# WiFi_BT.net
KiCad netlist of a schematic drawn in Altium Designer
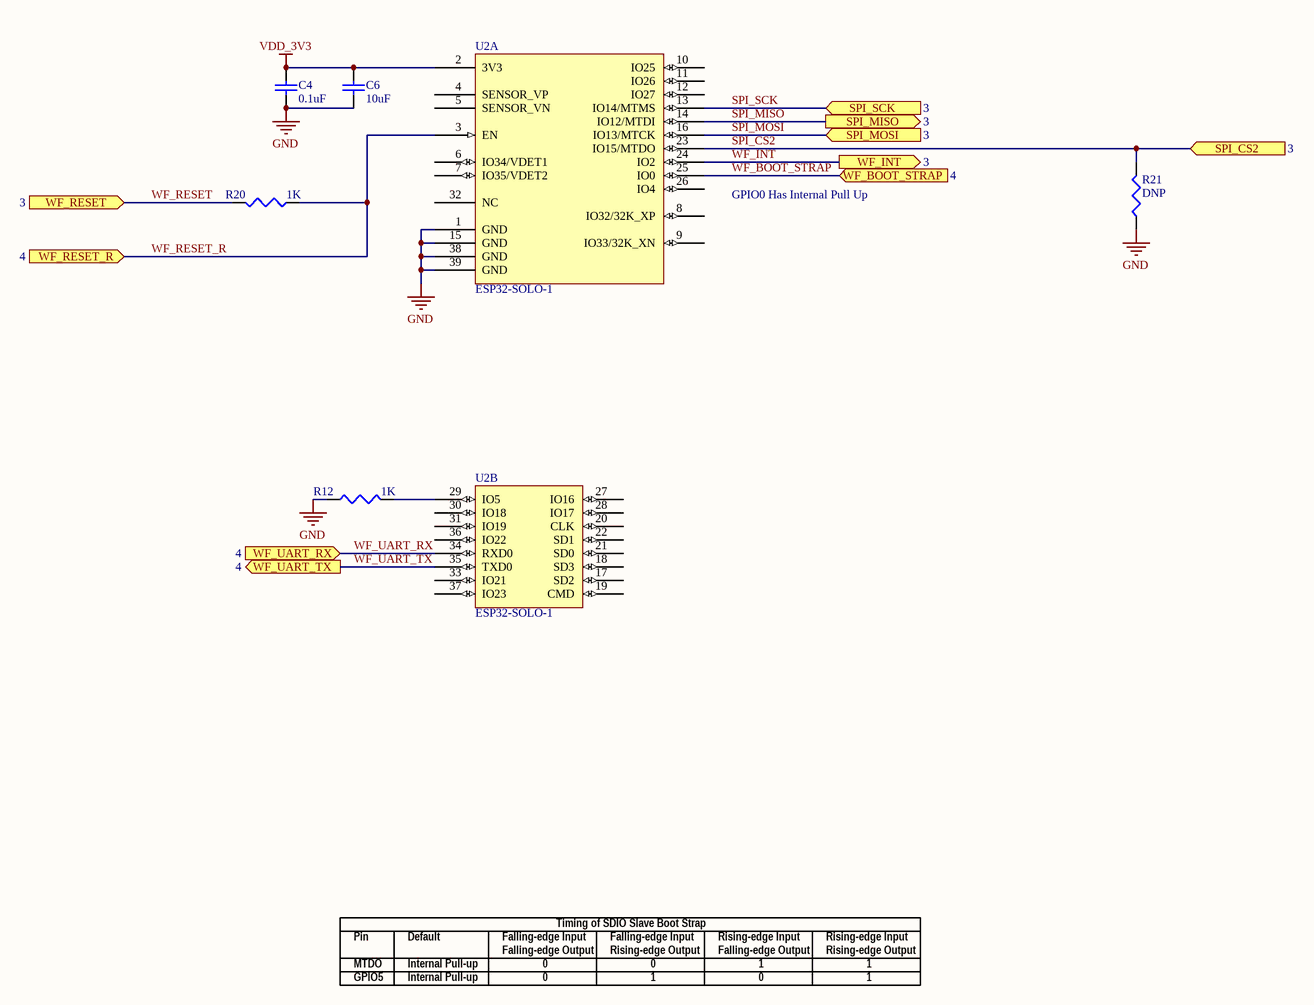
[diagram p0: WiFi_BT.SchDoc]

(export (version "E")
  (design (tool "Eeschema 10.0.6"))
  (components
    (comp (ref "C4")
      (value "0.1uF")
      (footprint "C0402")
      (description "0.10µF 16V Ceramic Capacitor X7R 0402")
      (fields
        (field (name "PART NUMBER") "C0100004")
        (field (name "MANUFACTURER") "Samsung Electro-Mechanics")
      )
      (libsource (lib "PartLibrary") (part "Capacitor - non polarized"))
    )
    (comp (ref "C6")
      (value "10uF")
      (footprint "C0603")
      (description "CAP CER 10UF 10V X5R 0603")
      (fields (field (name "PART NUMBER") "C0100033") (field (name "MANUFACTURER") "Murata Electronics"))
      (libsource (lib "PartLibrary") (part "Capacitor - non polarized"))
    )
    (comp (ref "R12")
      (value "1K")
      (footprint "R0402")
      (description "RES SMD 1K OHM 1% 1/16W 0402")
      (fields (field (name "PART NUMBER") "R0000019") (field (name "MANUFACTURER") "Yageo"))
      (libsource (lib "PartLibrary") (part "Resistor"))
    )
    (comp (ref "R20")
      (value "1K")
      (footprint "R0402")
      (description "RES SMD 1K OHM 1% 1/16W 0402")
      (fields (field (name "PART NUMBER") "R0000019") (field (name "MANUFACTURER") "Yageo"))
      (libsource (lib "PartLibrary") (part "Resistor"))
    )
    (comp (ref "R21")
      (value "DNP")
      (footprint "R0402")
      (description "RES SMD 1K OHM 1% 1/16W 0402")
      (fields (field (name "PART NUMBER") "R0000019") (field (name "MANUFACTURER") "Yageo"))
      (libsource (lib "PartLibrary") (part "Resistor"))
    )
    (comp (ref "U2")
      (value "ESP32-SOLO-1")
      (footprint "ESP-WROOM-32")
      (description "WiFi 802.11n + BT4.2 Chipset Module Single Core with PCB Antenna 18mmx25.5mm")
      (fields (field (name "PART NUMBER") "U0000061") (field (name "MANUFACTURER") "Espressif Systems"))
      (libsource (lib "PartLibrary") (part "ESP32_WROOM"))
    )
  )
  (nets
    (net (code "1") (name "/SPI_CS2") (class "Default")
      (node (ref "R21") (pin "2") (pinfunction "2_2") (pintype "passive"))
      (node (ref "U2") (pin "23") (pinfunction "IO15/MTDO_23") (pintype "bidirectional"))
    )
    (net (code "2") (name "/SPI_MISO") (class "Default")
      (node (ref "U2") (pin "14") (pinfunction "IO12/MTDI_14") (pintype "bidirectional"))
    )
    (net (code "3") (name "/SPI_MOSI") (class "Default")
      (node (ref "U2") (pin "16") (pinfunction "IO13/MTCK_16") (pintype "bidirectional"))
    )
    (net (code "4") (name "/SPI_SCK") (class "Default")
      (node (ref "U2") (pin "13") (pinfunction "IO14/MTMS_13") (pintype "bidirectional"))
    )
    (net (code "5") (name "/WF_BOOT_STRAP") (class "Default")
      (node (ref "U2") (pin "25") (pinfunction "IO0_25") (pintype "bidirectional"))
    )
    (net (code "6") (name "/WF_INT") (class "Default")
      (node (ref "U2") (pin "24") (pinfunction "IO2_24") (pintype "bidirectional"))
    )
    (net (code "7") (name "/WF_RESET") (class "Default")
      (node (ref "R20") (pin "2") (pinfunction "2_2") (pintype "passive"))
    )
    (net (code "8") (name "/WF_RESET_R") (class "Default")
      (node (ref "R20") (pin "1") (pinfunction "1_1") (pintype "passive"))
      (node (ref "U2") (pin "3") (pinfunction "EN_3") (pintype "input"))
    )
    (net (code "9") (name "/WF_UART_RX") (class "Default")
      (node (ref "U2") (pin "34") (pinfunction "RXD0_34") (pintype "bidirectional"))
    )
    (net (code "10") (name "/WF_UART_TX") (class "Default")
      (node (ref "U2") (pin "35") (pinfunction "TXD0_35") (pintype "bidirectional"))
    )
    (net (code "11") (name "GND") (class "Default")
      (node (ref "C4") (pin "1") (pinfunction "1_1") (pintype "passive"))
      (node (ref "C6") (pin "2") (pinfunction "2_2") (pintype "passive"))
      (node (ref "R12") (pin "1") (pinfunction "1_1") (pintype "passive"))
      (node (ref "R21") (pin "1") (pinfunction "1_1") (pintype "passive"))
      (node (ref "U2") (pin "1") (pinfunction "GND_1") (pintype "passive"))
      (node (ref "U2") (pin "15") (pinfunction "GND_15") (pintype "passive"))
      (node (ref "U2") (pin "38") (pinfunction "GND_38") (pintype "passive"))
      (node (ref "U2") (pin "39") (pinfunction "GND_39") (pintype "passive"))
    )
    (net (code "12") (name "Net-(U2B-IO5)") (class "Default")
      (node (ref "R12") (pin "2") (pinfunction "2_2") (pintype "passive"))
      (node (ref "U2") (pin "29") (pinfunction "IO5_29") (pintype "bidirectional"))
    )
    (net (code "13") (name "VDD_3V3") (class "Default")
      (node (ref "C4") (pin "2") (pinfunction "2_2") (pintype "passive"))
      (node (ref "C6") (pin "1") (pinfunction "1_1") (pintype "passive"))
      (node (ref "U2") (pin "2") (pinfunction "3V3_2") (pintype "power_in"))
    )
    (net (code "14") (name "unconnected-(U2A-IO4-Pad26)") (class "Default")
      (node (ref "U2") (pin "26") (pinfunction "IO4_26") (pintype "bidirectional"))
    )
    (net (code "15") (name "unconnected-(U2A-IO25-Pad10)") (class "Default")
      (node (ref "U2") (pin "10") (pinfunction "IO25_10") (pintype "bidirectional"))
    )
    (net (code "16") (name "unconnected-(U2A-IO26-Pad11)") (class "Default")
      (node (ref "U2") (pin "11") (pinfunction "IO26_11") (pintype "bidirectional"))
    )
    (net (code "17") (name "unconnected-(U2A-IO27-Pad12)") (class "Default")
      (node (ref "U2") (pin "12") (pinfunction "IO27_12") (pintype "bidirectional"))
    )
    (net (code "18") (name "unconnected-(U2A-IO32{slash}32K_XP-Pad8)") (class "Default")
      (node (ref "U2") (pin "8") (pinfunction "IO32/32K_XP_8") (pintype "bidirectional"))
    )
    (net (code "19") (name "unconnected-(U2A-IO33{slash}32K_XN-Pad9)") (class "Default")
      (node (ref "U2") (pin "9") (pinfunction "IO33/32K_XN_9") (pintype "bidirectional"))
    )
    (net (code "20") (name "unconnected-(U2A-IO34{slash}VDET1-Pad6)") (class "Default")
      (node (ref "U2") (pin "6") (pinfunction "IO34/VDET1_6") (pintype "bidirectional"))
    )
    (net (code "21") (name "unconnected-(U2A-IO35{slash}VDET2-Pad7)") (class "Default")
      (node (ref "U2") (pin "7") (pinfunction "IO35/VDET2_7") (pintype "bidirectional"))
    )
    (net (code "22") (name "unconnected-(U2A-NC-Pad32)") (class "Default")
      (node (ref "U2") (pin "32") (pinfunction "NC_32") (pintype "passive"))
    )
    (net (code "23") (name "unconnected-(U2A-SENSOR_VN-Pad5)") (class "Default")
      (node (ref "U2") (pin "5") (pinfunction "SENSOR_VN_5") (pintype "passive"))
    )
    (net (code "24") (name "unconnected-(U2A-SENSOR_VP-Pad4)") (class "Default")
      (node (ref "U2") (pin "4") (pinfunction "SENSOR_VP_4") (pintype "passive"))
    )
    (net (code "25") (name "unconnected-(U2B-CLK-Pad20)") (class "Default")
      (node (ref "U2") (pin "20") (pinfunction "CLK_20") (pintype "bidirectional"))
    )
    (net (code "26") (name "unconnected-(U2B-CMD-Pad19)") (class "Default")
      (node (ref "U2") (pin "19") (pinfunction "CMD_19") (pintype "bidirectional"))
    )
    (net (code "27") (name "unconnected-(U2B-IO16-Pad27)") (class "Default")
      (node (ref "U2") (pin "27") (pinfunction "IO16_27") (pintype "bidirectional"))
    )
    (net (code "28") (name "unconnected-(U2B-IO17-Pad28)") (class "Default")
      (node (ref "U2") (pin "28") (pinfunction "IO17_28") (pintype "bidirectional"))
    )
    (net (code "29") (name "unconnected-(U2B-IO18-Pad30)") (class "Default")
      (node (ref "U2") (pin "30") (pinfunction "IO18_30") (pintype "bidirectional"))
    )
    (net (code "30") (name "unconnected-(U2B-IO19-Pad31)") (class "Default")
      (node (ref "U2") (pin "31") (pinfunction "IO19_31") (pintype "bidirectional"))
    )
    (net (code "31") (name "unconnected-(U2B-IO21-Pad33)") (class "Default")
      (node (ref "U2") (pin "33") (pinfunction "IO21_33") (pintype "bidirectional"))
    )
    (net (code "32") (name "unconnected-(U2B-IO22-Pad36)") (class "Default")
      (node (ref "U2") (pin "36") (pinfunction "IO22_36") (pintype "bidirectional"))
    )
    (net (code "33") (name "unconnected-(U2B-IO23-Pad37)") (class "Default")
      (node (ref "U2") (pin "37") (pinfunction "IO23_37") (pintype "bidirectional"))
    )
    (net (code "34") (name "unconnected-(U2B-SD0-Pad21)") (class "Default")
      (node (ref "U2") (pin "21") (pinfunction "SD0_21") (pintype "bidirectional"))
    )
    (net (code "35") (name "unconnected-(U2B-SD1-Pad22)") (class "Default")
      (node (ref "U2") (pin "22") (pinfunction "SD1_22") (pintype "bidirectional"))
    )
    (net (code "36") (name "unconnected-(U2B-SD2-Pad17)") (class "Default")
      (node (ref "U2") (pin "17") (pinfunction "SD2_17") (pintype "bidirectional"))
    )
    (net (code "37") (name "unconnected-(U2B-SD3-Pad18)") (class "Default")
      (node (ref "U2") (pin "18") (pinfunction "SD3_18") (pintype "bidirectional"))
    )
  )
)
